# PowerReceiver.net
KiCad netlist of a schematic drawn in EAGLE
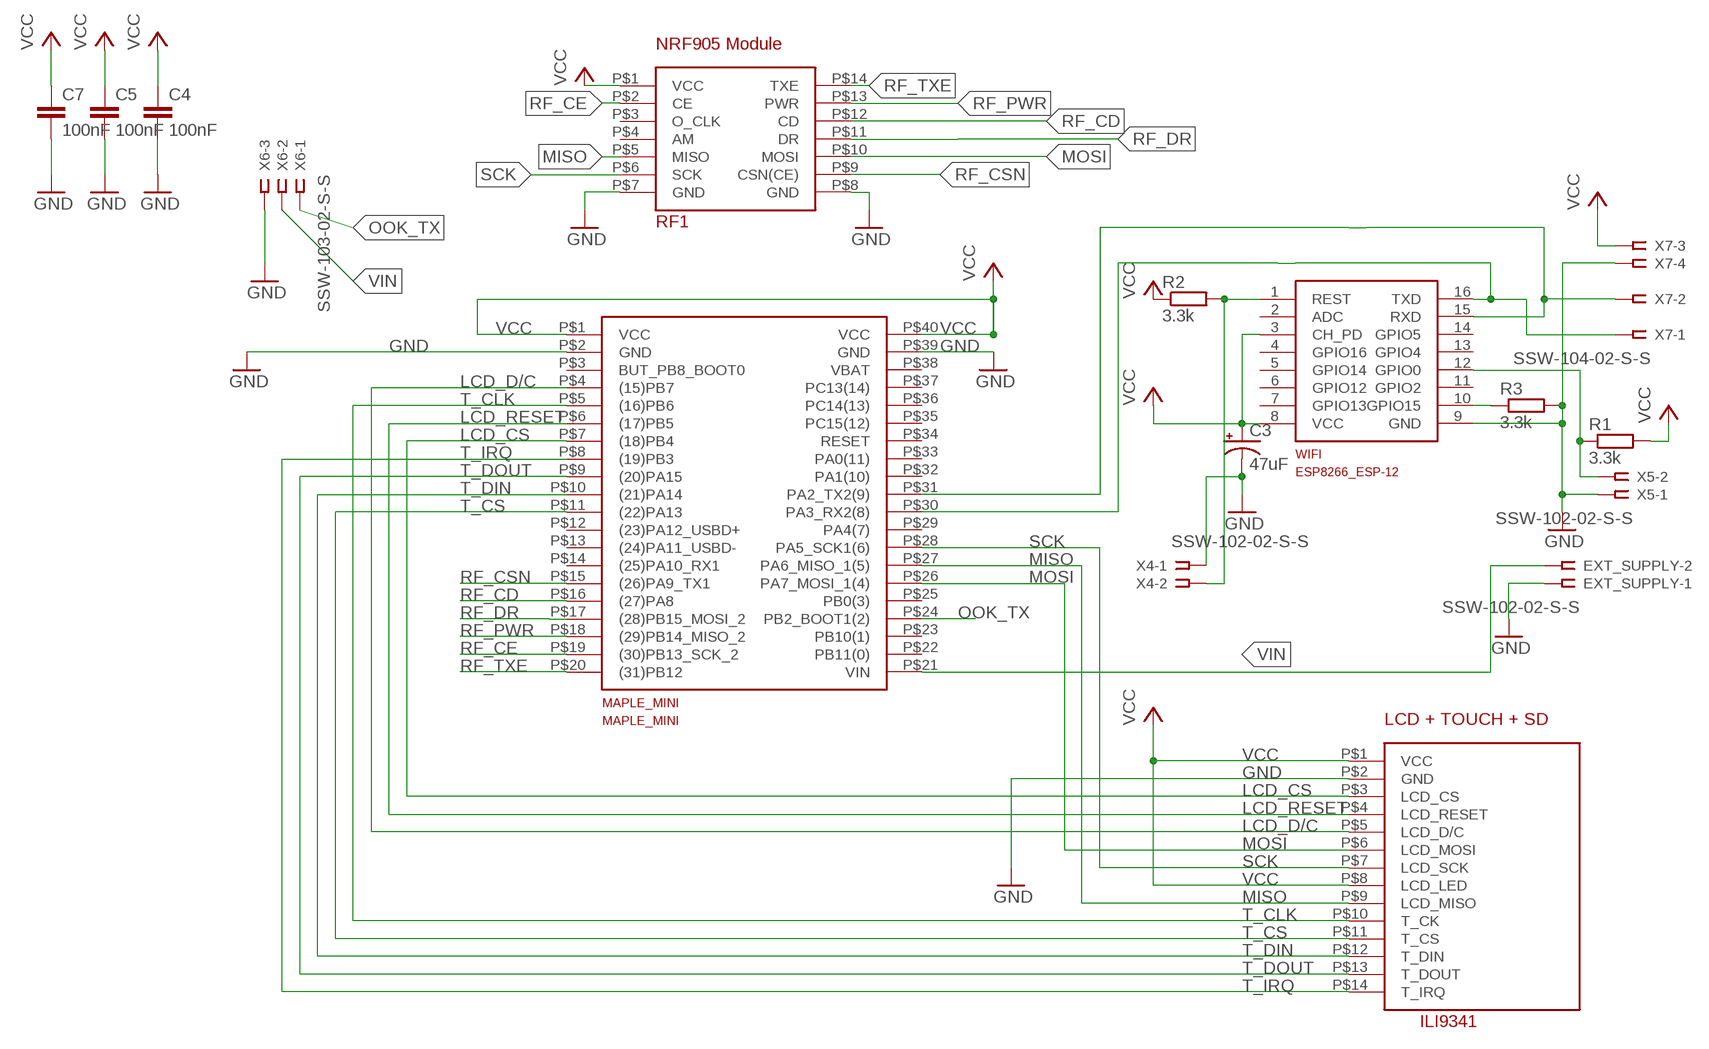
[diagram p0: schematic, sheet 1]

(export (version "E")
  (design (tool "Eeschema 10.0.6"))
  (components
    (comp (ref "C3")
      (value "47uF")
      (footprint "eagle-import:E5-8,5")
      (libsource (lib "eagle-import") (part "CPOL-USE5-8.5"))
    )
    (comp (ref "C4")
      (value "100nF")
      (footprint "eagle-import:C050-035X075")
      (libsource (lib "eagle-import") (part "C-EU050-035X075"))
    )
    (comp (ref "C5")
      (value "100nF")
      (footprint "eagle-import:C050-035X075")
      (libsource (lib "eagle-import") (part "C-EU050-035X075"))
    )
    (comp (ref "C7")
      (value "100nF")
      (footprint "eagle-import:C050-035X075")
      (libsource (lib "eagle-import") (part "C-EU050-035X075"))
    )
    (comp (ref "EXT_SUPPLY")
      (value "SSW-102-02-S-S")
      (footprint "eagle-import:SSW-102-02-S-S")
      (libsource (lib "eagle-import") (part "SSW-102-02-S-S"))
    )
    (comp (ref "ILI9341")
      (value "ILI9341_TOUCH_SD")
      (footprint "eagle-import:2.4_INCH")
      (libsource (lib "eagle-import") (part "ILI9341_TOUCH_SD"))
    )
    (comp (ref "MAPLE_MINI")
      (value "MAPLE_MINI")
      (footprint "eagle-import:MAPLE_MINI")
      (libsource (lib "eagle-import") (part "MAPLE_MINI"))
    )
    (comp (ref "R1")
      (value "3.3k")
      (footprint "eagle-import:0309V")
      (libsource (lib "eagle-import") (part "R-EU_0309/V"))
    )
    (comp (ref "R2")
      (value "3.3k")
      (footprint "eagle-import:0309V")
      (libsource (lib "eagle-import") (part "R-EU_0309/V"))
    )
    (comp (ref "R3")
      (value "3.3k")
      (footprint "eagle-import:0309V")
      (libsource (lib "eagle-import") (part "R-EU_0309/V"))
    )
    (comp (ref "RF1")
      (value "NRF905_MODULE")
      (footprint "eagle-import:PIN14")
      (libsource (lib "eagle-import") (part "NRF905_MODULE"))
    )
    (comp (ref "WIFI")
      (value "ESP8266-12")
      (footprint "eagle-import:ESP8266-ESP12")
      (libsource (lib "eagle-import") (part "ESP8266-12GPIO04/05_CORRECTED"))
    )
    (comp (ref "X4")
      (value "SSW-102-02-S-S")
      (footprint "eagle-import:SSW-102-02-S-S")
      (libsource (lib "eagle-import") (part "SSW-102-02-S-S"))
    )
    (comp (ref "X5")
      (value "SSW-102-02-S-S")
      (footprint "eagle-import:SSW-102-02-S-S")
      (libsource (lib "eagle-import") (part "SSW-102-02-S-S"))
    )
    (comp (ref "X6")
      (value "SSW-103-02-S-S")
      (footprint "eagle-import:SSW-103-02-S-S")
      (libsource (lib "eagle-import") (part "SSW-103-02-S-S"))
    )
    (comp (ref "X7")
      (value "SSW-104-02-S-S")
      (footprint "eagle-import:SSW-104-02-S-S")
      (libsource (lib "eagle-import") (part "SSW-104-02-S-S"))
    )
  )
  (nets
    (net (code "1") (name "/LCD_CS") (class "Default")
      (node (ref "ILI9341") (pin "P$3") (pinfunction "LCD_CS_P$3") (pintype "input"))
      (node (ref "MAPLE_MINI") (pin "P$7") (pinfunction "(18)PB4_P$7") (pintype "bidirectional"))
    )
    (net (code "2") (name "/LCD_D{slash}C") (class "Default")
      (node (ref "ILI9341") (pin "P$5") (pinfunction "LCD_D/C_P$5") (pintype "input"))
      (node (ref "MAPLE_MINI") (pin "P$4") (pinfunction "(15)PB7_P$4") (pintype "bidirectional"))
    )
    (net (code "3") (name "/LCD_RESET") (class "Default")
      (node (ref "ILI9341") (pin "P$4") (pinfunction "LCD_RESET_P$4") (pintype "input"))
      (node (ref "MAPLE_MINI") (pin "P$6") (pinfunction "(17)PB5_P$6") (pintype "bidirectional"))
    )
    (net (code "4") (name "/T_CLK") (class "Default")
      (node (ref "ILI9341") (pin "P$10") (pinfunction "T_CK_P$10") (pintype "input"))
      (node (ref "MAPLE_MINI") (pin "P$5") (pinfunction "(16)PB6_P$5") (pintype "bidirectional"))
    )
    (net (code "5") (name "/T_CS") (class "Default")
      (node (ref "ILI9341") (pin "P$11") (pinfunction "T_CS_P$11") (pintype "bidirectional"))
      (node (ref "MAPLE_MINI") (pin "P$11") (pinfunction "(22)PA13_P$11") (pintype "bidirectional"))
    )
    (net (code "6") (name "/T_DIN") (class "Default")
      (node (ref "ILI9341") (pin "P$12") (pinfunction "T_DIN_P$12") (pintype "input"))
      (node (ref "MAPLE_MINI") (pin "P$10") (pinfunction "(21)PA14_P$10") (pintype "bidirectional"))
    )
    (net (code "7") (name "/T_DOUT") (class "Default")
      (node (ref "ILI9341") (pin "P$13") (pinfunction "T_DOUT_P$13") (pintype "output"))
      (node (ref "MAPLE_MINI") (pin "P$9") (pinfunction "(20)PA15_P$9") (pintype "bidirectional"))
    )
    (net (code "8") (name "/T_IRQ") (class "Default")
      (node (ref "ILI9341") (pin "P$14") (pinfunction "T_IRQ_P$14") (pintype "output"))
      (node (ref "MAPLE_MINI") (pin "P$8") (pinfunction "(19)PB3_P$8") (pintype "bidirectional"))
    )
    (net (code "9") (name "GND") (class "Default")
      (node (ref "C3") (pin "-") (pinfunction "-_-") (pintype "passive"))
      (node (ref "C4") (pin "2") (pinfunction "2_2") (pintype "passive"))
      (node (ref "C5") (pin "2") (pinfunction "2_2") (pintype "passive"))
      (node (ref "C7") (pin "2") (pinfunction "2_2") (pintype "passive"))
      (node (ref "EXT_SUPPLY") (pin "1") (pinfunction "1_1") (pintype "passive"))
      (node (ref "ILI9341") (pin "P$2") (pinfunction "GND_P$2") (pintype "power_in"))
      (node (ref "MAPLE_MINI") (pin "P$2") (pinfunction "GND_P$2") (pintype "power_in"))
      (node (ref "MAPLE_MINI") (pin "P$39") (pinfunction "GND_P$39") (pintype "power_in"))
      (node (ref "R3") (pin "2") (pinfunction "2_2") (pintype "passive"))
      (node (ref "RF1") (pin "P$7") (pinfunction "GND_P$7") (pintype "power_in"))
      (node (ref "RF1") (pin "P$8") (pinfunction "GND_P$8") (pintype "power_in"))
      (node (ref "WIFI") (pin "9") (pinfunction "GND_9") (pintype "bidirectional"))
      (node (ref "X4") (pin "1") (pinfunction "1_1") (pintype "passive"))
      (node (ref "X5") (pin "1") (pinfunction "1_1") (pintype "passive"))
      (node (ref "X6") (pin "3") (pinfunction "1_3") (pintype "passive"))
      (node (ref "X7") (pin "4") (pinfunction "1_4") (pintype "passive"))
    )
    (net (code "10") (name "MISO") (class "Default")
      (node (ref "ILI9341") (pin "P$9") (pinfunction "LCD_MISO_P$9") (pintype "bidirectional"))
      (node (ref "MAPLE_MINI") (pin "P$27") (pinfunction "PA6_MISO_1(5)_P$27") (pintype "bidirectional"))
      (node (ref "RF1") (pin "P$5") (pinfunction "MISO_P$5") (pintype "output"))
    )
    (net (code "11") (name "MOSI") (class "Default")
      (node (ref "ILI9341") (pin "P$6") (pinfunction "LCD_MOSI_P$6") (pintype "input"))
      (node (ref "MAPLE_MINI") (pin "P$26") (pinfunction "PA7_MOSI_1(4)_P$26") (pintype "bidirectional"))
      (node (ref "RF1") (pin "P$10") (pinfunction "MOSI_P$10") (pintype "input"))
    )
    (net (code "12") (name "Net-(MAPLE_MINI-PA2_TX2(9))") (class "Default")
      (node (ref "MAPLE_MINI") (pin "P$31") (pinfunction "PA2_TX2(9)_P$31") (pintype "bidirectional"))
      (node (ref "WIFI") (pin "15") (pinfunction "RXD_15") (pintype "bidirectional"))
      (node (ref "X7") (pin "2") (pinfunction "1_2") (pintype "passive"))
    )
    (net (code "13") (name "Net-(MAPLE_MINI-PA3_RX2(8))") (class "Default")
      (node (ref "MAPLE_MINI") (pin "P$30") (pinfunction "PA3_RX2(8)_P$30") (pintype "bidirectional"))
      (node (ref "WIFI") (pin "16") (pinfunction "TXD_16") (pintype "bidirectional"))
      (node (ref "X7") (pin "1") (pinfunction "1_1") (pintype "passive"))
    )
    (net (code "14") (name "Net-(WIFI-GPIO0)") (class "Default")
      (node (ref "R1") (pin "1") (pinfunction "1_1") (pintype "passive"))
      (node (ref "WIFI") (pin "12") (pinfunction "GPIO0_12") (pintype "bidirectional"))
      (node (ref "X5") (pin "2") (pinfunction "1_2") (pintype "passive"))
    )
    (net (code "15") (name "Net-(WIFI-GPIO15)") (class "Default")
      (node (ref "R3") (pin "1") (pinfunction "1_1") (pintype "passive"))
      (node (ref "WIFI") (pin "10") (pinfunction "GPIO15_10") (pintype "bidirectional"))
    )
    (net (code "16") (name "Net-(WIFI-REST)") (class "Default")
      (node (ref "R2") (pin "2") (pinfunction "2_2") (pintype "passive"))
      (node (ref "WIFI") (pin "1") (pinfunction "REST_1") (pintype "bidirectional"))
      (node (ref "X4") (pin "2") (pinfunction "1_2") (pintype "passive"))
    )
    (net (code "17") (name "OOK_TX") (class "Default")
      (node (ref "MAPLE_MINI") (pin "P$24") (pinfunction "PB2_BOOT1(2)_P$24") (pintype "bidirectional"))
      (node (ref "X6") (pin "1") (pinfunction "1_1") (pintype "passive"))
    )
    (net (code "18") (name "RF_CD") (class "Default")
      (node (ref "MAPLE_MINI") (pin "P$16") (pinfunction "(27)PA8_P$16") (pintype "bidirectional"))
      (node (ref "RF1") (pin "P$12") (pinfunction "CD_P$12") (pintype "bidirectional"))
    )
    (net (code "19") (name "RF_CE") (class "Default")
      (node (ref "MAPLE_MINI") (pin "P$19") (pinfunction "(30)PB13_SCK_2_P$19") (pintype "bidirectional"))
      (node (ref "RF1") (pin "P$2") (pinfunction "CE_P$2") (pintype "input"))
    )
    (net (code "20") (name "RF_CSN") (class "Default")
      (node (ref "MAPLE_MINI") (pin "P$15") (pinfunction "(26)PA9_TX1_P$15") (pintype "bidirectional"))
      (node (ref "RF1") (pin "P$9") (pinfunction "CSN(CE)_P$9") (pintype "input"))
    )
    (net (code "21") (name "RF_DR") (class "Default")
      (node (ref "MAPLE_MINI") (pin "P$17") (pinfunction "(28)PB15_MOSI_2_P$17") (pintype "bidirectional"))
      (node (ref "RF1") (pin "P$11") (pinfunction "DR_P$11") (pintype "bidirectional"))
    )
    (net (code "22") (name "RF_PWR") (class "Default")
      (node (ref "MAPLE_MINI") (pin "P$18") (pinfunction "(29)PB14_MISO_2_P$18") (pintype "bidirectional"))
      (node (ref "RF1") (pin "P$13") (pinfunction "PWR_P$13") (pintype "bidirectional"))
    )
    (net (code "23") (name "RF_TXE") (class "Default")
      (node (ref "MAPLE_MINI") (pin "P$20") (pinfunction "(31)PB12_P$20") (pintype "bidirectional"))
      (node (ref "RF1") (pin "P$14") (pinfunction "TXE_P$14") (pintype "bidirectional"))
    )
    (net (code "24") (name "SCK") (class "Default")
      (node (ref "ILI9341") (pin "P$7") (pinfunction "LCD_SCK_P$7") (pintype "input"))
      (node (ref "MAPLE_MINI") (pin "P$28") (pinfunction "PA5_SCK1(6)_P$28") (pintype "bidirectional"))
      (node (ref "RF1") (pin "P$6") (pinfunction "SCK_P$6") (pintype "bidirectional"))
    )
    (net (code "25") (name "VCC") (class "Default")
      (node (ref "C3") (pin "+") (pinfunction "+_+") (pintype "passive"))
      (node (ref "C4") (pin "1") (pinfunction "1_1") (pintype "passive"))
      (node (ref "C5") (pin "1") (pinfunction "1_1") (pintype "passive"))
      (node (ref "C7") (pin "1") (pinfunction "1_1") (pintype "passive"))
      (node (ref "ILI9341") (pin "P$1") (pinfunction "VCC_P$1") (pintype "power_in"))
      (node (ref "ILI9341") (pin "P$8") (pinfunction "LCD_LED_P$8") (pintype "bidirectional"))
      (node (ref "MAPLE_MINI") (pin "P$1") (pinfunction "VCC_P$1") (pintype "bidirectional"))
      (node (ref "MAPLE_MINI") (pin "P$40") (pinfunction "VCC_P$40") (pintype "bidirectional"))
      (node (ref "R1") (pin "2") (pinfunction "2_2") (pintype "passive"))
      (node (ref "R2") (pin "1") (pinfunction "1_1") (pintype "passive"))
      (node (ref "RF1") (pin "P$1") (pinfunction "VCC_P$1") (pintype "power_in"))
      (node (ref "WIFI") (pin "3") (pinfunction "CH_PD_3") (pintype "bidirectional"))
      (node (ref "WIFI") (pin "8") (pinfunction "VCC_8") (pintype "bidirectional"))
      (node (ref "X7") (pin "3") (pinfunction "1_3") (pintype "passive"))
    )
    (net (code "26") (name "VIN") (class "Default")
      (node (ref "EXT_SUPPLY") (pin "2") (pinfunction "1_2") (pintype "passive"))
      (node (ref "MAPLE_MINI") (pin "P$21") (pinfunction "VIN_P$21") (pintype "power_in"))
      (node (ref "X6") (pin "2") (pinfunction "1_2") (pintype "passive"))
    )
    (net (code "27") (name "unconnected-(MAPLE_MINI-(23)PA12_USBD+-PadP$12)") (class "Default")
      (node (ref "MAPLE_MINI") (pin "P$12") (pinfunction "(23)PA12_USBD+_P$12") (pintype "bidirectional"))
    )
    (net (code "28") (name "unconnected-(MAPLE_MINI-(24)PA11_USBD--PadP$13)") (class "Default")
      (node (ref "MAPLE_MINI") (pin "P$13") (pinfunction "(24)PA11_USBD-_P$13") (pintype "bidirectional"))
    )
    (net (code "29") (name "unconnected-(MAPLE_MINI-(25)PA10_RX1-PadP$14)") (class "Default")
      (node (ref "MAPLE_MINI") (pin "P$14") (pinfunction "(25)PA10_RX1_P$14") (pintype "bidirectional"))
    )
    (net (code "30") (name "unconnected-(MAPLE_MINI-BUT_PB8_BOOT0-PadP$3)") (class "Default")
      (node (ref "MAPLE_MINI") (pin "P$3") (pinfunction "BUT_PB8_BOOT0_P$3") (pintype "bidirectional"))
    )
    (net (code "31") (name "unconnected-(MAPLE_MINI-PA0(11)-PadP$33)") (class "Default")
      (node (ref "MAPLE_MINI") (pin "P$33") (pinfunction "PA0(11)_P$33") (pintype "bidirectional"))
    )
    (net (code "32") (name "unconnected-(MAPLE_MINI-PA1(10)-PadP$32)") (class "Default")
      (node (ref "MAPLE_MINI") (pin "P$32") (pinfunction "PA1(10)_P$32") (pintype "bidirectional"))
    )
    (net (code "33") (name "unconnected-(MAPLE_MINI-PA4(7)-PadP$29)") (class "Default")
      (node (ref "MAPLE_MINI") (pin "P$29") (pinfunction "PA4(7)_P$29") (pintype "bidirectional"))
    )
    (net (code "34") (name "unconnected-(MAPLE_MINI-PB0(3)-PadP$25)") (class "Default")
      (node (ref "MAPLE_MINI") (pin "P$25") (pinfunction "PB0(3)_P$25") (pintype "bidirectional"))
    )
    (net (code "35") (name "unconnected-(MAPLE_MINI-PB10(1)-PadP$23)") (class "Default")
      (node (ref "MAPLE_MINI") (pin "P$23") (pinfunction "PB10(1)_P$23") (pintype "bidirectional"))
    )
    (net (code "36") (name "unconnected-(MAPLE_MINI-PB11(0)-PadP$22)") (class "Default")
      (node (ref "MAPLE_MINI") (pin "P$22") (pinfunction "PB11(0)_P$22") (pintype "bidirectional"))
    )
    (net (code "37") (name "unconnected-(MAPLE_MINI-PC13(14)-PadP$37)") (class "Default")
      (node (ref "MAPLE_MINI") (pin "P$37") (pinfunction "PC13(14)_P$37") (pintype "bidirectional"))
    )
    (net (code "38") (name "unconnected-(MAPLE_MINI-PC14(13)-PadP$36)") (class "Default")
      (node (ref "MAPLE_MINI") (pin "P$36") (pinfunction "PC14(13)_P$36") (pintype "bidirectional"))
    )
    (net (code "39") (name "unconnected-(MAPLE_MINI-PC15(12)-PadP$35)") (class "Default")
      (node (ref "MAPLE_MINI") (pin "P$35") (pinfunction "PC15(12)_P$35") (pintype "bidirectional"))
    )
    (net (code "40") (name "unconnected-(MAPLE_MINI-RESET-PadP$34)") (class "Default")
      (node (ref "MAPLE_MINI") (pin "P$34") (pinfunction "RESET_P$34") (pintype "bidirectional"))
    )
    (net (code "41") (name "unconnected-(MAPLE_MINI-VBAT-PadP$38)") (class "Default")
      (node (ref "MAPLE_MINI") (pin "P$38") (pinfunction "VBAT_P$38") (pintype "bidirectional"))
    )
    (net (code "42") (name "unconnected-(RF1-AM-PadP$4)") (class "Default")
      (node (ref "RF1") (pin "P$4") (pinfunction "AM_P$4") (pintype "output"))
    )
    (net (code "43") (name "unconnected-(RF1-O_CLK-PadP$3)") (class "Default")
      (node (ref "RF1") (pin "P$3") (pinfunction "O_CLK_P$3") (pintype "output"))
    )
    (net (code "44") (name "unconnected-(WIFI-ADC-Pad2)") (class "Default")
      (node (ref "WIFI") (pin "2") (pinfunction "ADC_2") (pintype "bidirectional"))
    )
    (net (code "45") (name "unconnected-(WIFI-GPIO2-Pad11)") (class "Default")
      (node (ref "WIFI") (pin "11") (pinfunction "GPIO2_11") (pintype "bidirectional"))
    )
    (net (code "46") (name "unconnected-(WIFI-GPIO4-Pad13)") (class "Default")
      (node (ref "WIFI") (pin "13") (pinfunction "GPIO4_13") (pintype "bidirectional"))
    )
    (net (code "47") (name "unconnected-(WIFI-GPIO5-Pad14)") (class "Default")
      (node (ref "WIFI") (pin "14") (pinfunction "GPIO5_14") (pintype "bidirectional"))
    )
    (net (code "48") (name "unconnected-(WIFI-GPIO12-Pad6)") (class "Default")
      (node (ref "WIFI") (pin "6") (pinfunction "GPIO12_6") (pintype "bidirectional"))
    )
    (net (code "49") (name "unconnected-(WIFI-GPIO13-Pad7)") (class "Default")
      (node (ref "WIFI") (pin "7") (pinfunction "GPIO13_7") (pintype "bidirectional"))
    )
    (net (code "50") (name "unconnected-(WIFI-GPIO14-Pad5)") (class "Default")
      (node (ref "WIFI") (pin "5") (pinfunction "GPIO14_5") (pintype "bidirectional"))
    )
    (net (code "51") (name "unconnected-(WIFI-GPIO16-Pad4)") (class "Default")
      (node (ref "WIFI") (pin "4") (pinfunction "GPIO16_4") (pintype "bidirectional"))
    )
  )
)
